# sp6641.net
KiCad netlist of a schematic drawn in EAGLE
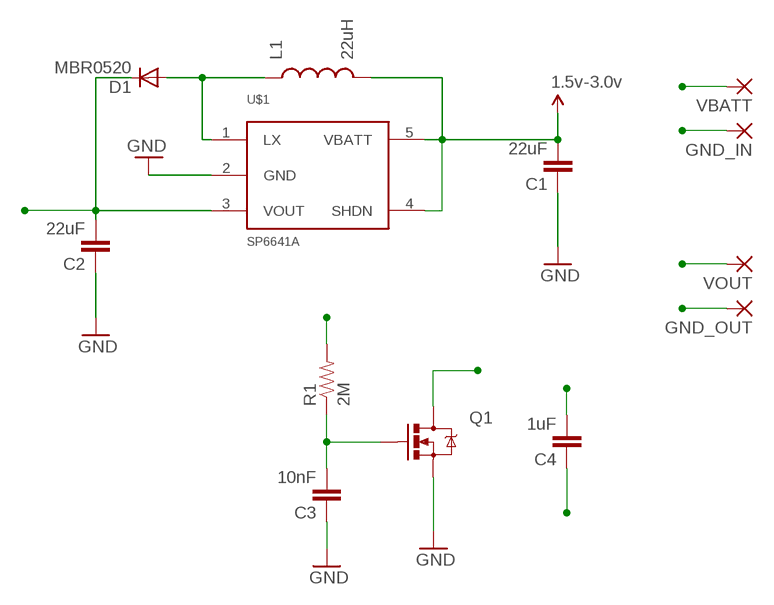
[diagram p0: schematic, sheet 1]

(export (version "E")
  (design (tool "Eeschema 10.0.6"))
  (components
    (comp (ref "C1")
      (value "22uF")
      (footprint "eagle-import:0805")
      (libsource (lib "eagle-import") (part "CAP0805"))
    )
    (comp (ref "C2")
      (value "22uF")
      (footprint "eagle-import:0805")
      (libsource (lib "eagle-import") (part "CAP0805"))
    )
    (comp (ref "C3")
      (value "10nF")
      (footprint "eagle-import:0805")
      (libsource (lib "eagle-import") (part "CAP0805"))
    )
    (comp (ref "C4")
      (value "1uF")
      (footprint "eagle-import:1206")
      (libsource (lib "eagle-import") (part "CAP1206"))
    )
    (comp (ref "D1")
      (value "MBR0520")
      (footprint "eagle-import:SOD123")
      (libsource (lib "eagle-import") (part "MBR0520LT"))
    )
    (comp (ref "GND_IN")
      (value "WIREPAD2,54/1,0")
      (footprint "eagle-import:2,54_1,0")
      (libsource (lib "eagle-import") (part "WIREPAD2,54/1,0"))
    )
    (comp (ref "GND_OUT")
      (value "WIREPAD2,54/1,0")
      (footprint "eagle-import:2,54_1,0")
      (libsource (lib "eagle-import") (part "WIREPAD2,54/1,0"))
    )
    (comp (ref "L1")
      (value "22uH")
      (footprint "eagle-import:CR54")
      (libsource (lib "eagle-import") (part "INDUCTORCR54"))
    )
    (comp (ref "Q1")
      (value "MOSFET-NCHANNELSMD")
      (footprint "eagle-import:SOT23-3")
      (libsource (lib "eagle-import") (part "MOSFET-NCHANNELSMD"))
    )
    (comp (ref "R1")
      (value "2M")
      (footprint "eagle-import:0805")
      (libsource (lib "eagle-import") (part "RESISTOR0805-RES"))
    )
    (comp (ref "U$1")
      (value "SP6641A")
      (footprint "eagle-import:SOT23-5")
      (libsource (lib "eagle-import") (part "SP6641SP6641A/B"))
    )
    (comp (ref "VBATT")
      (value "WIREPAD2,54/1,0")
      (footprint "eagle-import:2,54_1,0")
      (libsource (lib "eagle-import") (part "WIREPAD2,54/1,0"))
    )
    (comp (ref "VOUT")
      (value "WIREPAD2,54/1,0")
      (footprint "eagle-import:2,54_1,0")
      (libsource (lib "eagle-import") (part "WIREPAD2,54/1,0"))
    )
  )
  (nets
    (net (code "1") (name "/GND_OUT") (class "Default")
      (node (ref "C4") (pin "1") (pinfunction "1_1") (pintype "passive"))
      (node (ref "GND_OUT") (pin "1") (pinfunction "P_1") (pintype "passive"))
      (node (ref "Q1") (pin "3") (pinfunction "D_3") (pintype "passive"))
    )
    (net (code "2") (name "/VOUT") (class "Default")
      (node (ref "C2") (pin "2") (pinfunction "2_2") (pintype "passive"))
      (node (ref "C4") (pin "2") (pinfunction "2_2") (pintype "passive"))
      (node (ref "D1") (pin "C") (pinfunction "C_C") (pintype "passive"))
      (node (ref "R1") (pin "2") (pinfunction "2_2") (pintype "passive"))
      (node (ref "U$1") (pin "3") (pinfunction "VOUT_3") (pintype "bidirectional"))
      (node (ref "VOUT") (pin "1") (pinfunction "P_1") (pintype "passive"))
    )
    (net (code "3") (name "1.5v-3.0v") (class "Default")
      (node (ref "C1") (pin "2") (pinfunction "2_2") (pintype "passive"))
      (node (ref "L1") (pin "P$2") (pinfunction "2_P$2") (pintype "passive"))
      (node (ref "U$1") (pin "4") (pinfunction "SHDN_4") (pintype "bidirectional"))
      (node (ref "U$1") (pin "5") (pinfunction "VBATT_5") (pintype "bidirectional"))
      (node (ref "VBATT") (pin "1") (pinfunction "P_1") (pintype "passive"))
    )
    (net (code "4") (name "GND") (class "Default")
      (node (ref "C1") (pin "1") (pinfunction "1_1") (pintype "passive"))
      (node (ref "C2") (pin "1") (pinfunction "1_1") (pintype "passive"))
      (node (ref "C3") (pin "1") (pinfunction "1_1") (pintype "passive"))
      (node (ref "GND_IN") (pin "1") (pinfunction "P_1") (pintype "passive"))
      (node (ref "Q1") (pin "2") (pinfunction "S_2") (pintype "passive"))
      (node (ref "U$1") (pin "2") (pinfunction "GND_2") (pintype "bidirectional"))
    )
    (net (code "5") (name "Net-(L1-1)") (class "Default")
      (node (ref "D1") (pin "A") (pinfunction "A_A") (pintype "passive"))
      (node (ref "L1") (pin "P$1") (pinfunction "1_P$1") (pintype "passive"))
      (node (ref "U$1") (pin "1") (pinfunction "LX_1") (pintype "bidirectional"))
    )
    (net (code "6") (name "Net-(Q1-G)") (class "Default")
      (node (ref "C3") (pin "2") (pinfunction "2_2") (pintype "passive"))
      (node (ref "Q1") (pin "1") (pinfunction "G_1") (pintype "passive"))
      (node (ref "R1") (pin "1") (pinfunction "1_1") (pintype "passive"))
    )
  )
)
